# Dew-Point-Control.net
KiCad netlist of a schematic drawn in EAGLE
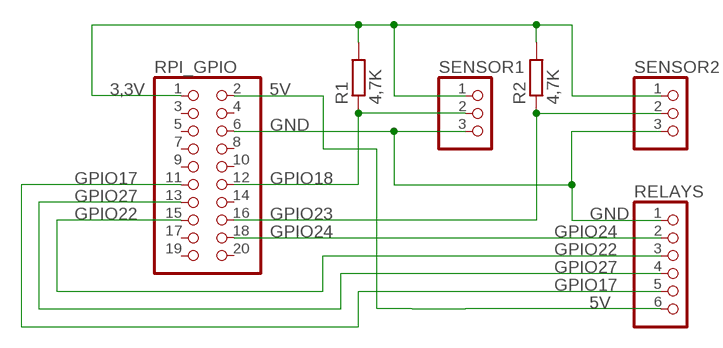
[diagram p0: schematic, sheet 1]

(export (version "E")
  (design (tool "Eeschema 10.0.6"))
  (components
    (comp (ref "R1")
      (value "4,7K")
      (footprint "eagle-import:0207_10")
      (libsource (lib "eagle-import") (part "R-EU_0207/10"))
    )
    (comp (ref "R2")
      (value "4,7K")
      (footprint "eagle-import:0207_10")
      (libsource (lib "eagle-import") (part "R-EU_0207/10"))
    )
    (comp (ref "RELAYS")
      (value "PINHD-1X6")
      (footprint "eagle-import:1X06")
      (libsource (lib "eagle-import") (part "PINHD-1X6"))
    )
    (comp (ref "RPI_GPIO")
      (value "PINHD-2X10")
      (footprint "eagle-import:2X10")
      (libsource (lib "eagle-import") (part "PINHD-2X10"))
    )
    (comp (ref "SENSOR1")
      (value "PINHD-1X3")
      (footprint "eagle-import:1X03")
      (libsource (lib "eagle-import") (part "PINHD-1X3"))
    )
    (comp (ref "SENSOR2")
      (value "PINHD-1X3")
      (footprint "eagle-import:1X03")
      (libsource (lib "eagle-import") (part "PINHD-1X3"))
    )
  )
  (nets
    (net (code "1") (name "/3,3V") (class "Default")
      (node (ref "R1") (pin "2") (pinfunction "2_2") (pintype "passive"))
      (node (ref "R2") (pin "2") (pinfunction "2_2") (pintype "passive"))
      (node (ref "RPI_GPIO") (pin "1") (pinfunction "1_1") (pintype "passive"))
      (node (ref "SENSOR1") (pin "1") (pinfunction "1_1") (pintype "passive"))
      (node (ref "SENSOR2") (pin "1") (pinfunction "1_1") (pintype "passive"))
    )
    (net (code "2") (name "/5V") (class "Default")
      (node (ref "RELAYS") (pin "6") (pinfunction "6_6") (pintype "passive"))
      (node (ref "RPI_GPIO") (pin "2") (pinfunction "2_2") (pintype "passive"))
    )
    (net (code "3") (name "/GND") (class "Default")
      (node (ref "RELAYS") (pin "1") (pinfunction "1_1") (pintype "passive"))
      (node (ref "RPI_GPIO") (pin "6") (pinfunction "6_6") (pintype "passive"))
      (node (ref "SENSOR1") (pin "3") (pinfunction "3_3") (pintype "passive"))
      (node (ref "SENSOR2") (pin "3") (pinfunction "3_3") (pintype "passive"))
    )
    (net (code "4") (name "/GPIO17") (class "Default")
      (node (ref "RELAYS") (pin "5") (pinfunction "5_5") (pintype "passive"))
      (node (ref "RPI_GPIO") (pin "11") (pinfunction "11_11") (pintype "passive"))
    )
    (net (code "5") (name "/GPIO18") (class "Default")
      (node (ref "R1") (pin "1") (pinfunction "1_1") (pintype "passive"))
      (node (ref "RPI_GPIO") (pin "12") (pinfunction "12_12") (pintype "passive"))
      (node (ref "SENSOR1") (pin "2") (pinfunction "2_2") (pintype "passive"))
    )
    (net (code "6") (name "/GPIO22") (class "Default")
      (node (ref "RELAYS") (pin "3") (pinfunction "3_3") (pintype "passive"))
      (node (ref "RPI_GPIO") (pin "15") (pinfunction "15_15") (pintype "passive"))
    )
    (net (code "7") (name "/GPIO23") (class "Default")
      (node (ref "R2") (pin "1") (pinfunction "1_1") (pintype "passive"))
      (node (ref "RPI_GPIO") (pin "16") (pinfunction "16_16") (pintype "passive"))
      (node (ref "SENSOR2") (pin "2") (pinfunction "2_2") (pintype "passive"))
    )
    (net (code "8") (name "/GPIO24") (class "Default")
      (node (ref "RELAYS") (pin "2") (pinfunction "2_2") (pintype "passive"))
      (node (ref "RPI_GPIO") (pin "18") (pinfunction "18_18") (pintype "passive"))
    )
    (net (code "9") (name "/GPIO27") (class "Default")
      (node (ref "RELAYS") (pin "4") (pinfunction "4_4") (pintype "passive"))
      (node (ref "RPI_GPIO") (pin "13") (pinfunction "13_13") (pintype "passive"))
    )
    (net (code "10") (name "unconnected-(RPI_GPIO-Pad3)") (class "Default")
      (node (ref "RPI_GPIO") (pin "3") (pinfunction "3_3") (pintype "passive"))
    )
    (net (code "11") (name "unconnected-(RPI_GPIO-Pad4)") (class "Default")
      (node (ref "RPI_GPIO") (pin "4") (pinfunction "4_4") (pintype "passive"))
    )
    (net (code "12") (name "unconnected-(RPI_GPIO-Pad5)") (class "Default")
      (node (ref "RPI_GPIO") (pin "5") (pinfunction "5_5") (pintype "passive"))
    )
    (net (code "13") (name "unconnected-(RPI_GPIO-Pad7)") (class "Default")
      (node (ref "RPI_GPIO") (pin "7") (pinfunction "7_7") (pintype "passive"))
    )
    (net (code "14") (name "unconnected-(RPI_GPIO-Pad8)") (class "Default")
      (node (ref "RPI_GPIO") (pin "8") (pinfunction "8_8") (pintype "passive"))
    )
    (net (code "15") (name "unconnected-(RPI_GPIO-Pad9)") (class "Default")
      (node (ref "RPI_GPIO") (pin "9") (pinfunction "9_9") (pintype "passive"))
    )
    (net (code "16") (name "unconnected-(RPI_GPIO-Pad10)") (class "Default")
      (node (ref "RPI_GPIO") (pin "10") (pinfunction "10_10") (pintype "passive"))
    )
    (net (code "17") (name "unconnected-(RPI_GPIO-Pad14)") (class "Default")
      (node (ref "RPI_GPIO") (pin "14") (pinfunction "14_14") (pintype "passive"))
    )
    (net (code "18") (name "unconnected-(RPI_GPIO-Pad17)") (class "Default")
      (node (ref "RPI_GPIO") (pin "17") (pinfunction "17_17") (pintype "passive"))
    )
    (net (code "19") (name "unconnected-(RPI_GPIO-Pad19)") (class "Default")
      (node (ref "RPI_GPIO") (pin "19") (pinfunction "19_19") (pintype "passive"))
    )
    (net (code "20") (name "unconnected-(RPI_GPIO-Pad20)") (class "Default")
      (node (ref "RPI_GPIO") (pin "20") (pinfunction "20_20") (pintype "passive"))
    )
  )
)
